# MM_Capstone.net
KiCad netlist of a schematic drawn in EAGLE
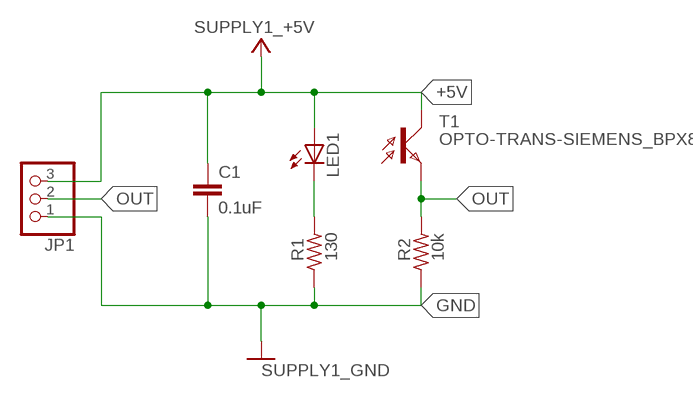
[diagram p0: schematic, sheet 1]

(export (version "E")
  (design (tool "Eeschema 10.0.6"))
  (components
    (comp (ref "C1")
      (value "0.1uF")
      (footprint "eagle-import:RCL_C1206")
      (libsource (lib "eagle-import") (part "RCL_C-EUC1206"))
    )
    (comp (ref "JP1")
      (value "PINHEAD_PINHD-1X3")
      (footprint "eagle-import:PINHEAD_1X03")
      (libsource (lib "eagle-import") (part "PINHEAD_PINHD-1X3"))
    )
    (comp (ref "LED1")
      (value "LED_LED5MM")
      (footprint "eagle-import:LED_LED5MM")
      (libsource (lib "eagle-import") (part "LED_LED5MM"))
    )
    (comp (ref "R1")
      (value "130")
      (footprint "eagle-import:RCL_R1206")
      (libsource (lib "eagle-import") (part "RCL_R-US_R1206"))
    )
    (comp (ref "R2")
      (value "10k")
      (footprint "eagle-import:RCL_R1206")
      (libsource (lib "eagle-import") (part "RCL_R-US_R1206"))
    )
    (comp (ref "T1")
      (value "OPTO-TRANS-SIEMENS_BPX81")
      (footprint "eagle-import:OPTO-TRANS-SIEMENS_BPX81")
      (libsource (lib "eagle-import") (part "OPTO-TRANS-SIEMENS_BPX81"))
    )
  )
  (nets
    (net (code "1") (name "+5V") (class "Default")
      (node (ref "C1") (pin "1") (pinfunction "1_1") (pintype "passive"))
      (node (ref "JP1") (pin "3") (pinfunction "3_3") (pintype "passive"))
      (node (ref "LED1") (pin "A") (pinfunction "A_A") (pintype "passive"))
      (node (ref "T1") (pin "C") (pinfunction "C_C") (pintype "passive"))
    )
    (net (code "2") (name "GND") (class "Default")
      (node (ref "C1") (pin "2") (pinfunction "2_2") (pintype "passive"))
      (node (ref "JP1") (pin "1") (pinfunction "1_1") (pintype "passive"))
      (node (ref "R1") (pin "1") (pinfunction "1_1") (pintype "passive"))
      (node (ref "R2") (pin "1") (pinfunction "1_1") (pintype "passive"))
    )
    (net (code "3") (name "Net-(LED1-C)") (class "Default")
      (node (ref "LED1") (pin "K") (pinfunction "C_K") (pintype "passive"))
      (node (ref "R1") (pin "2") (pinfunction "2_2") (pintype "passive"))
    )
    (net (code "4") (name "OUT") (class "Default")
      (node (ref "JP1") (pin "2") (pinfunction "2_2") (pintype "passive"))
      (node (ref "R2") (pin "2") (pinfunction "2_2") (pintype "passive"))
      (node (ref "T1") (pin "E") (pinfunction "E_E") (pintype "passive"))
    )
  )
)
